# KCInput_Attenuator_V0_1.net
KiCad netlist of a schematic drawn in Altium Designer
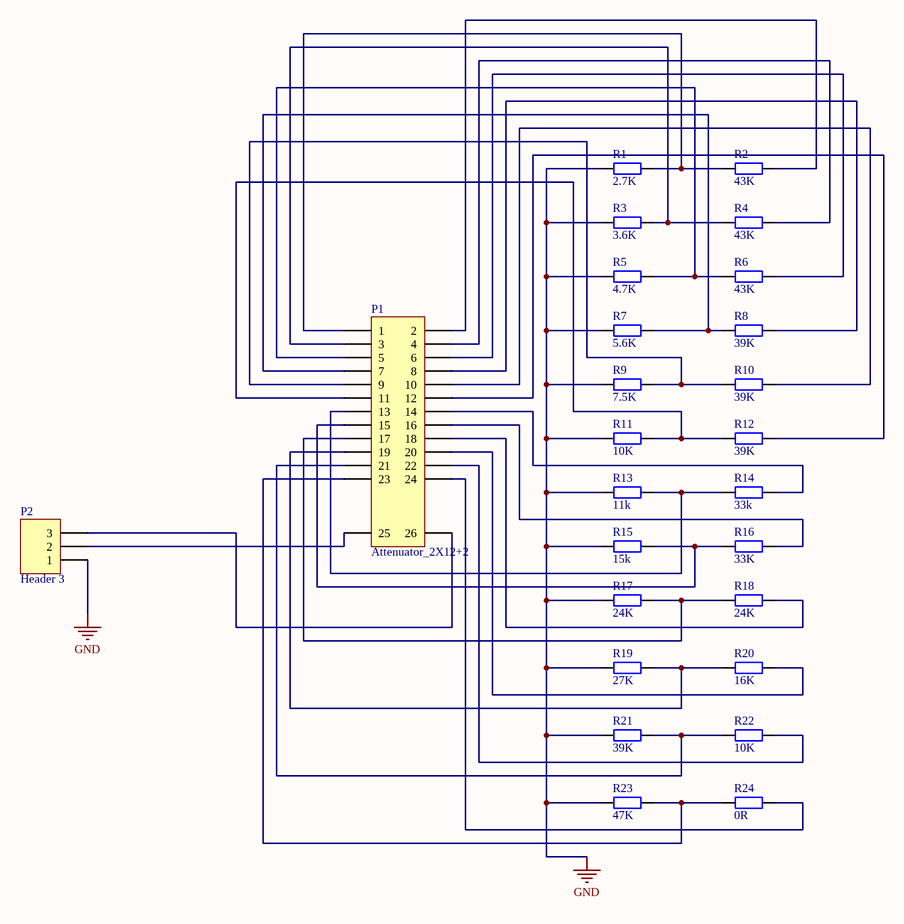
[diagram p0: KCInput_Attenuator_V0.1.SchDoc]

(export (version "E")
  (design (tool "Eeschema 10.0.6"))
  (components
    (comp (ref "P1")
      (value "Attenuator_2X12+2")
      (footprint "Attenuator_2X13")
      (description "Attenuator  12-Pin, Dual row, 2 Out")
      (fields (field (name "PUBLISHER") "Altium Limited"))
      (libsource (lib "Connectors") (part "Attenuator_2X12+2"))
    )
    (comp (ref "P2")
      (value "Header 3")
      (footprint "HDR1X3")
      (description "Header, 3-Pin")
      (fields (field (name "PUBLISHER") "Altium Limited"))
      (libsource (lib "Connectors") (part "Header 3"))
    )
    (comp (ref "R1")
      (value "2.7K")
      (footprint "RS 1/4W")
      (description "直插色环电阻")
      (fields (field (name "版权归属") "源创客"))
      (libsource (lib "电阻-电容-电感") (part "R-CRR"))
    )
    (comp (ref "R2")
      (value "43K")
      (footprint "RS 1/4W")
      (description "直插色环电阻")
      (fields (field (name "版权归属") "源创客"))
      (libsource (lib "电阻-电容-电感") (part "R-CRR"))
    )
    (comp (ref "R3")
      (value "3.6K")
      (footprint "RS 1/4W")
      (description "直插色环电阻")
      (fields (field (name "版权归属") "源创客"))
      (libsource (lib "电阻-电容-电感") (part "R-CRR"))
    )
    (comp (ref "R4")
      (value "43K")
      (footprint "RS 1/4W")
      (description "直插色环电阻")
      (fields (field (name "版权归属") "源创客"))
      (libsource (lib "电阻-电容-电感") (part "R-CRR"))
    )
    (comp (ref "R5")
      (value "4.7K")
      (footprint "RS 1/4W")
      (description "直插色环电阻")
      (fields (field (name "版权归属") "源创客"))
      (libsource (lib "电阻-电容-电感") (part "R-CRR"))
    )
    (comp (ref "R6")
      (value "43K")
      (footprint "RS 1/4W")
      (description "直插色环电阻")
      (fields (field (name "版权归属") "源创客"))
      (libsource (lib "电阻-电容-电感") (part "R-CRR"))
    )
    (comp (ref "R7")
      (value "5.6K")
      (footprint "RS 1/4W")
      (description "直插色环电阻")
      (fields (field (name "版权归属") "源创客"))
      (libsource (lib "电阻-电容-电感") (part "R-CRR"))
    )
    (comp (ref "R8")
      (value "39K")
      (footprint "RS 1/4W")
      (description "直插色环电阻")
      (fields (field (name "版权归属") "源创客"))
      (libsource (lib "电阻-电容-电感") (part "R-CRR"))
    )
    (comp (ref "R9")
      (value "7.5K")
      (footprint "RS 1/4W")
      (description "直插色环电阻")
      (fields (field (name "版权归属") "源创客"))
      (libsource (lib "电阻-电容-电感") (part "R-CRR"))
    )
    (comp (ref "R10")
      (value "39K")
      (footprint "RS 1/4W")
      (description "直插色环电阻")
      (fields (field (name "版权归属") "源创客"))
      (libsource (lib "电阻-电容-电感") (part "R-CRR"))
    )
    (comp (ref "R11")
      (value "10K")
      (footprint "RS 1/4W")
      (description "直插色环电阻")
      (fields (field (name "版权归属") "源创客"))
      (libsource (lib "电阻-电容-电感") (part "R-CRR"))
    )
    (comp (ref "R12")
      (value "39K")
      (footprint "RS 1/4W")
      (description "直插色环电阻")
      (fields (field (name "版权归属") "源创客"))
      (libsource (lib "电阻-电容-电感") (part "R-CRR"))
    )
    (comp (ref "R13")
      (value "11k")
      (footprint "RS 1/4W")
      (description "直插色环电阻")
      (fields (field (name "版权归属") "源创客"))
      (libsource (lib "电阻-电容-电感") (part "R-CRR"))
    )
    (comp (ref "R14")
      (value "33k")
      (footprint "RS 1/4W")
      (description "直插色环电阻")
      (fields (field (name "版权归属") "源创客"))
      (libsource (lib "电阻-电容-电感") (part "R-CRR"))
    )
    (comp (ref "R15")
      (value "15k")
      (footprint "RS 1/4W")
      (description "直插色环电阻")
      (fields (field (name "版权归属") "源创客"))
      (libsource (lib "电阻-电容-电感") (part "R-CRR"))
    )
    (comp (ref "R16")
      (value "33K")
      (footprint "RS 1/4W")
      (description "直插色环电阻")
      (fields (field (name "版权归属") "源创客"))
      (libsource (lib "电阻-电容-电感") (part "R-CRR"))
    )
    (comp (ref "R17")
      (value "24K")
      (footprint "RS 1/4W")
      (description "直插色环电阻")
      (fields (field (name "版权归属") "源创客"))
      (libsource (lib "电阻-电容-电感") (part "R-CRR"))
    )
    (comp (ref "R18")
      (value "24K")
      (footprint "RS 1/4W")
      (description "直插色环电阻")
      (fields (field (name "版权归属") "源创客"))
      (libsource (lib "电阻-电容-电感") (part "R-CRR"))
    )
    (comp (ref "R19")
      (value "27K")
      (footprint "RS 1/4W")
      (description "直插色环电阻")
      (fields (field (name "版权归属") "源创客"))
      (libsource (lib "电阻-电容-电感") (part "R-CRR"))
    )
    (comp (ref "R20")
      (value "16K")
      (footprint "RS 1/4W")
      (description "直插色环电阻")
      (fields (field (name "版权归属") "源创客"))
      (libsource (lib "电阻-电容-电感") (part "R-CRR"))
    )
    (comp (ref "R21")
      (value "39K")
      (footprint "RS 1/4W")
      (description "直插色环电阻")
      (fields (field (name "版权归属") "源创客"))
      (libsource (lib "电阻-电容-电感") (part "R-CRR"))
    )
    (comp (ref "R22")
      (value "10K")
      (footprint "RS 1/4W")
      (description "直插色环电阻")
      (fields (field (name "版权归属") "源创客"))
      (libsource (lib "电阻-电容-电感") (part "R-CRR"))
    )
    (comp (ref "R23")
      (value "47K")
      (footprint "RS 1/4W")
      (description "直插色环电阻")
      (fields (field (name "版权归属") "源创客"))
      (libsource (lib "电阻-电容-电感") (part "R-CRR"))
    )
    (comp (ref "R24")
      (value "0R")
      (footprint "RS 1/4W")
      (description "直插色环电阻")
      (fields (field (name "版权归属") "源创客"))
      (libsource (lib "电阻-电容-电感") (part "R-CRR"))
    )
  )
  (nets
    (net (code "1") (name "GND") (class "Default")
      (node (ref "P2") (pin "1") (pinfunction "1_1") (pintype "passive"))
      (node (ref "R1") (pin "1") (pinfunction "1_1") (pintype "passive"))
      (node (ref "R11") (pin "1") (pinfunction "1_1") (pintype "passive"))
      (node (ref "R13") (pin "1") (pinfunction "1_1") (pintype "passive"))
      (node (ref "R15") (pin "1") (pinfunction "1_1") (pintype "passive"))
      (node (ref "R17") (pin "1") (pinfunction "1_1") (pintype "passive"))
      (node (ref "R19") (pin "1") (pinfunction "1_1") (pintype "passive"))
      (node (ref "R21") (pin "1") (pinfunction "1_1") (pintype "passive"))
      (node (ref "R23") (pin "1") (pinfunction "1_1") (pintype "passive"))
      (node (ref "R3") (pin "1") (pinfunction "1_1") (pintype "passive"))
      (node (ref "R5") (pin "1") (pinfunction "1_1") (pintype "passive"))
      (node (ref "R7") (pin "1") (pinfunction "1_1") (pintype "passive"))
      (node (ref "R9") (pin "1") (pinfunction "1_1") (pintype "passive"))
    )
    (net (code "2") (name "Net-(P1-Pad1)") (class "Default")
      (node (ref "P1") (pin "1") (pinfunction "1_1") (pintype "passive"))
      (node (ref "R1") (pin "2") (pinfunction "2_2") (pintype "passive"))
      (node (ref "R2") (pin "1") (pinfunction "1_1") (pintype "passive"))
    )
    (net (code "3") (name "Net-(P1-Pad2)") (class "Default")
      (node (ref "P1") (pin "2") (pinfunction "2_2") (pintype "passive"))
      (node (ref "R2") (pin "2") (pinfunction "2_2") (pintype "passive"))
    )
    (net (code "4") (name "Net-(P1-Pad3)") (class "Default")
      (node (ref "P1") (pin "3") (pinfunction "3_3") (pintype "passive"))
      (node (ref "R3") (pin "2") (pinfunction "2_2") (pintype "passive"))
      (node (ref "R4") (pin "1") (pinfunction "1_1") (pintype "passive"))
    )
    (net (code "5") (name "Net-(P1-Pad4)") (class "Default")
      (node (ref "P1") (pin "4") (pinfunction "4_4") (pintype "passive"))
      (node (ref "R4") (pin "2") (pinfunction "2_2") (pintype "passive"))
    )
    (net (code "6") (name "Net-(P1-Pad5)") (class "Default")
      (node (ref "P1") (pin "5") (pinfunction "5_5") (pintype "passive"))
      (node (ref "R5") (pin "2") (pinfunction "2_2") (pintype "passive"))
      (node (ref "R6") (pin "1") (pinfunction "1_1") (pintype "passive"))
    )
    (net (code "7") (name "Net-(P1-Pad6)") (class "Default")
      (node (ref "P1") (pin "6") (pinfunction "6_6") (pintype "passive"))
      (node (ref "R6") (pin "2") (pinfunction "2_2") (pintype "passive"))
    )
    (net (code "8") (name "Net-(P1-Pad7)") (class "Default")
      (node (ref "P1") (pin "7") (pinfunction "7_7") (pintype "passive"))
      (node (ref "R7") (pin "2") (pinfunction "2_2") (pintype "passive"))
      (node (ref "R8") (pin "1") (pinfunction "1_1") (pintype "passive"))
    )
    (net (code "9") (name "Net-(P1-Pad8)") (class "Default")
      (node (ref "P1") (pin "8") (pinfunction "8_8") (pintype "passive"))
      (node (ref "R8") (pin "2") (pinfunction "2_2") (pintype "passive"))
    )
    (net (code "10") (name "Net-(P1-Pad9)") (class "Default")
      (node (ref "P1") (pin "9") (pinfunction "9_9") (pintype "passive"))
      (node (ref "R10") (pin "1") (pinfunction "1_1") (pintype "passive"))
      (node (ref "R9") (pin "2") (pinfunction "2_2") (pintype "passive"))
    )
    (net (code "11") (name "Net-(P1-Pad10)") (class "Default")
      (node (ref "P1") (pin "10") (pinfunction "10_10") (pintype "passive"))
      (node (ref "R10") (pin "2") (pinfunction "2_2") (pintype "passive"))
    )
    (net (code "12") (name "Net-(P1-Pad11)") (class "Default")
      (node (ref "P1") (pin "11") (pinfunction "11_11") (pintype "passive"))
      (node (ref "R11") (pin "2") (pinfunction "2_2") (pintype "passive"))
      (node (ref "R12") (pin "1") (pinfunction "1_1") (pintype "passive"))
    )
    (net (code "13") (name "Net-(P1-Pad12)") (class "Default")
      (node (ref "P1") (pin "12") (pinfunction "12_12") (pintype "passive"))
      (node (ref "R12") (pin "2") (pinfunction "2_2") (pintype "passive"))
    )
    (net (code "14") (name "Net-(P1-Pad13)") (class "Default")
      (node (ref "P1") (pin "13") (pinfunction "13_13") (pintype "passive"))
      (node (ref "R13") (pin "2") (pinfunction "2_2") (pintype "passive"))
      (node (ref "R14") (pin "1") (pinfunction "1_1") (pintype "passive"))
    )
    (net (code "15") (name "Net-(P1-Pad14)") (class "Default")
      (node (ref "P1") (pin "14") (pinfunction "14_14") (pintype "passive"))
      (node (ref "R14") (pin "2") (pinfunction "2_2") (pintype "passive"))
    )
    (net (code "16") (name "Net-(P1-Pad15)") (class "Default")
      (node (ref "P1") (pin "15") (pinfunction "15_15") (pintype "passive"))
      (node (ref "R15") (pin "2") (pinfunction "2_2") (pintype "passive"))
      (node (ref "R16") (pin "1") (pinfunction "1_1") (pintype "passive"))
    )
    (net (code "17") (name "Net-(P1-Pad16)") (class "Default")
      (node (ref "P1") (pin "16") (pinfunction "16_16") (pintype "passive"))
      (node (ref "R16") (pin "2") (pinfunction "2_2") (pintype "passive"))
    )
    (net (code "18") (name "Net-(P1-Pad17)") (class "Default")
      (node (ref "P1") (pin "17") (pinfunction "17_17") (pintype "passive"))
      (node (ref "R17") (pin "2") (pinfunction "2_2") (pintype "passive"))
      (node (ref "R18") (pin "1") (pinfunction "1_1") (pintype "passive"))
    )
    (net (code "19") (name "Net-(P1-Pad18)") (class "Default")
      (node (ref "P1") (pin "18") (pinfunction "18_18") (pintype "passive"))
      (node (ref "R18") (pin "2") (pinfunction "2_2") (pintype "passive"))
    )
    (net (code "20") (name "Net-(P1-Pad19)") (class "Default")
      (node (ref "P1") (pin "19") (pinfunction "19_19") (pintype "passive"))
      (node (ref "R19") (pin "2") (pinfunction "2_2") (pintype "passive"))
      (node (ref "R20") (pin "1") (pinfunction "1_1") (pintype "passive"))
    )
    (net (code "21") (name "Net-(P1-Pad20)") (class "Default")
      (node (ref "P1") (pin "20") (pinfunction "20_20") (pintype "passive"))
      (node (ref "R20") (pin "2") (pinfunction "2_2") (pintype "passive"))
    )
    (net (code "22") (name "Net-(P1-Pad21)") (class "Default")
      (node (ref "P1") (pin "21") (pinfunction "21_21") (pintype "passive"))
      (node (ref "R21") (pin "2") (pinfunction "2_2") (pintype "passive"))
      (node (ref "R22") (pin "1") (pinfunction "1_1") (pintype "passive"))
    )
    (net (code "23") (name "Net-(P1-Pad22)") (class "Default")
      (node (ref "P1") (pin "22") (pinfunction "22_22") (pintype "passive"))
      (node (ref "R22") (pin "2") (pinfunction "2_2") (pintype "passive"))
    )
    (net (code "24") (name "Net-(P1-Pad23)") (class "Default")
      (node (ref "P1") (pin "23") (pinfunction "23_23") (pintype "passive"))
      (node (ref "R23") (pin "2") (pinfunction "2_2") (pintype "passive"))
      (node (ref "R24") (pin "1") (pinfunction "1_1") (pintype "passive"))
    )
    (net (code "25") (name "Net-(P1-Pad24)") (class "Default")
      (node (ref "P1") (pin "24") (pinfunction "24_24") (pintype "passive"))
      (node (ref "R24") (pin "2") (pinfunction "2_2") (pintype "passive"))
    )
    (net (code "26") (name "Net-(P1-Pad25)") (class "Default")
      (node (ref "P1") (pin "25") (pinfunction "25_25") (pintype "passive"))
      (node (ref "P2") (pin "2") (pinfunction "2_2") (pintype "passive"))
    )
    (net (code "27") (name "Net-(P1-Pad26)") (class "Default")
      (node (ref "P1") (pin "26") (pinfunction "26_26") (pintype "passive"))
      (node (ref "P2") (pin "3") (pinfunction "3_3") (pintype "passive"))
    )
  )
)
